# LIS331_Accelerometer.net
KiCad netlist of a schematic drawn in EAGLE
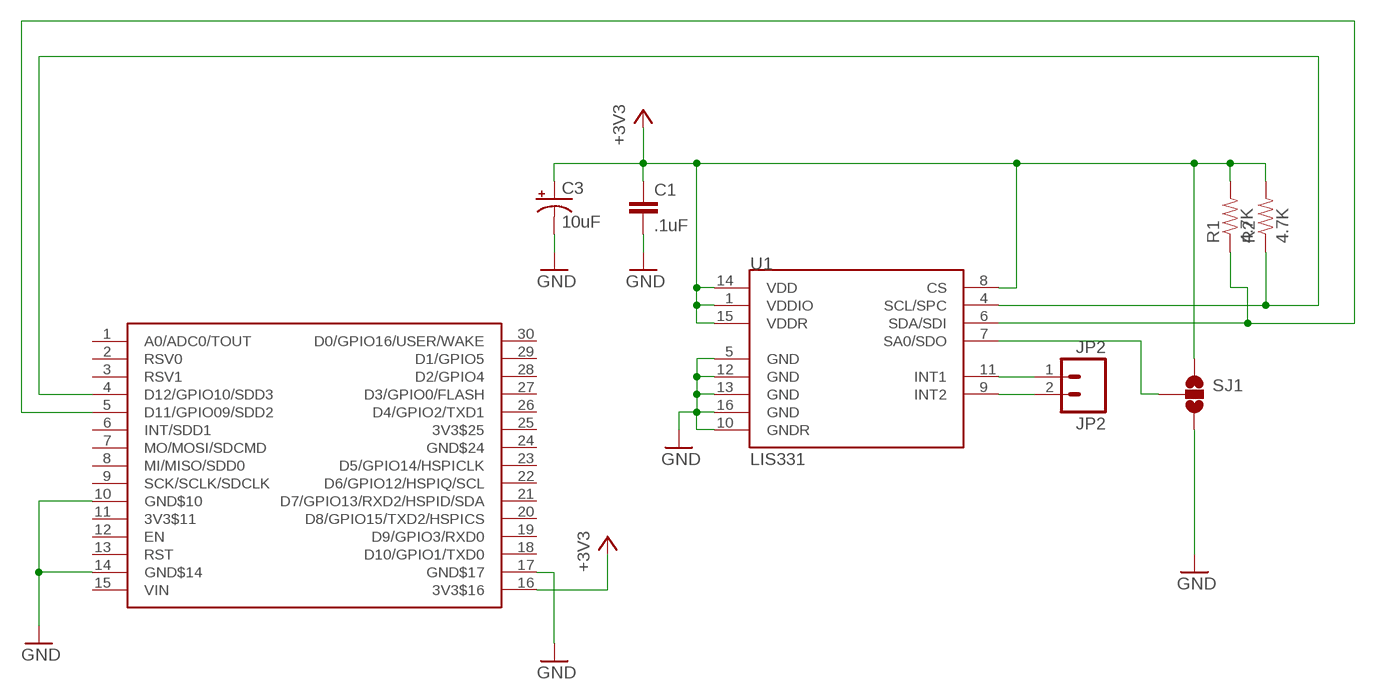
[diagram p0: schematic, sheet 1]

(export (version "E")
  (design (tool "Eeschema 10.0.6"))
  (components
    (comp (ref "C1")
      (value ".1uF")
      (footprint "eagle-import:0603-CAP")
      (libsource (lib "eagle-import") (part "CAP0603-CAP"))
    )
    (comp (ref "C3")
      (value "10uF")
      (footprint "eagle-import:EIA3216")
      (libsource (lib "eagle-import") (part "CAP_POL1206"))
    )
    (comp (ref "JP2")
      (value "JP2")
      (footprint "eagle-import:1X02")
      (libsource (lib "eagle-import") (part "M02PTH"))
    )
    (comp (ref "R1")
      (value "4.7K")
      (footprint "eagle-import:0603-RES")
      (libsource (lib "eagle-import") (part "RESISTOR0603-RES"))
    )
    (comp (ref "R2")
      (value "4.7K")
      (footprint "eagle-import:0603-RES")
      (libsource (lib "eagle-import") (part "RESISTOR0603-RES"))
    )
    (comp (ref "SJ1")
      (value "SOLDERJUMPER_2WAYT")
      (footprint "eagle-import:SJ_2")
      (libsource (lib "eagle-import") (part "SOLDERJUMPER_2WAYT"))
    )
    (comp (ref "U$2")
      (value "NERDSHIELD")
      (footprint "eagle-import:NERDUINO_STACK")
      (libsource (lib "eagle-import") (part "NERDSHIELD"))
    )
    (comp (ref "U1")
      (value "LIS331")
      (footprint "eagle-import:LGA16-3MM")
      (libsource (lib "eagle-import") (part "LIS331"))
    )
  )
  (nets
    (net (code "1") (name "+3V3") (class "Default")
      (node (ref "C1") (pin "1") (pinfunction "1_1") (pintype "passive"))
      (node (ref "C3") (pin "A") (pinfunction "+_A") (pintype "passive"))
      (node (ref "R1") (pin "2") (pinfunction "2_2") (pintype "passive"))
      (node (ref "R2") (pin "2") (pinfunction "2_2") (pintype "passive"))
      (node (ref "SJ1") (pin "1") (pinfunction "1_1") (pintype "passive"))
      (node (ref "U$2") (pin "16") (pinfunction "3V3$16_16") (pintype "bidirectional"))
      (node (ref "U1") (pin "1") (pinfunction "VDDIO_1") (pintype "bidirectional"))
      (node (ref "U1") (pin "14") (pinfunction "VDD_14") (pintype "bidirectional"))
      (node (ref "U1") (pin "15") (pinfunction "VDDR_15") (pintype "bidirectional"))
      (node (ref "U1") (pin "8") (pinfunction "CS_8") (pintype "bidirectional"))
    )
    (net (code "2") (name "GND") (class "Default")
      (node (ref "C1") (pin "2") (pinfunction "2_2") (pintype "passive"))
      (node (ref "C3") (pin "C") (pinfunction "-_C") (pintype "passive"))
      (node (ref "SJ1") (pin "3") (pinfunction "3_3") (pintype "passive"))
      (node (ref "U$2") (pin "10") (pinfunction "GND$10_10") (pintype "bidirectional"))
      (node (ref "U$2") (pin "14") (pinfunction "GND$14_14") (pintype "bidirectional"))
      (node (ref "U$2") (pin "17") (pinfunction "GND$17_17") (pintype "bidirectional"))
      (node (ref "U1") (pin "10") (pinfunction "GNDR_10") (pintype "bidirectional"))
      (node (ref "U1") (pin "12") (pinfunction "GND_12") (pintype "bidirectional"))
      (node (ref "U1") (pin "13") (pinfunction "GND_13") (pintype "bidirectional"))
      (node (ref "U1") (pin "16") (pinfunction "GND_16") (pintype "bidirectional"))
      (node (ref "U1") (pin "5") (pinfunction "GND_5") (pintype "bidirectional"))
    )
    (net (code "3") (name "Net-(U$2-D11{slash}GPIO09{slash}SDD2)") (class "Default")
      (node (ref "R1") (pin "1") (pinfunction "1_1") (pintype "passive"))
      (node (ref "U$2") (pin "5") (pinfunction "D11/GPIO09/SDD2_5") (pintype "bidirectional"))
      (node (ref "U1") (pin "6") (pinfunction "SDA/SDI_6") (pintype "bidirectional"))
    )
    (net (code "4") (name "Net-(U$2-D12{slash}GPIO10{slash}SDD3)") (class "Default")
      (node (ref "R2") (pin "1") (pinfunction "1_1") (pintype "passive"))
      (node (ref "U$2") (pin "4") (pinfunction "D12/GPIO10/SDD3_4") (pintype "bidirectional"))
      (node (ref "U1") (pin "4") (pinfunction "SCL/SPC_4") (pintype "bidirectional"))
    )
    (net (code "5") (name "Net-(U1-INT1)") (class "Default")
      (node (ref "JP2") (pin "1") (pinfunction "1_1") (pintype "passive"))
      (node (ref "U1") (pin "11") (pinfunction "INT1_11") (pintype "bidirectional"))
    )
    (net (code "6") (name "Net-(U1-INT2)") (class "Default")
      (node (ref "JP2") (pin "2") (pinfunction "2_2") (pintype "passive"))
      (node (ref "U1") (pin "9") (pinfunction "INT2_9") (pintype "bidirectional"))
    )
    (net (code "7") (name "Net-(U1-SA0{slash}SDO)") (class "Default")
      (node (ref "SJ1") (pin "2") (pinfunction "2_2") (pintype "passive"))
      (node (ref "U1") (pin "7") (pinfunction "SA0/SDO_7") (pintype "bidirectional"))
    )
    (net (code "8") (name "unconnected-(U$2-3V3$11-Pad11)") (class "Default")
      (node (ref "U$2") (pin "11") (pinfunction "3V3$11_11") (pintype "bidirectional"))
    )
    (net (code "9") (name "unconnected-(U$2-3V3$25-Pad25)") (class "Default")
      (node (ref "U$2") (pin "25") (pinfunction "3V3$25_25") (pintype "bidirectional"))
    )
    (net (code "10") (name "unconnected-(U$2-A0{slash}ADC0{slash}TOUT-Pad1)") (class "Default")
      (node (ref "U$2") (pin "1") (pinfunction "A0/ADC0/TOUT_1") (pintype "bidirectional"))
    )
    (net (code "11") (name "unconnected-(U$2-D0{slash}GPIO16{slash}USER{slash}WAKE-Pad30)") (class "Default")
      (node (ref "U$2") (pin "30") (pinfunction "D0/GPIO16/USER/WAKE_30") (pintype "bidirectional"))
    )
    (net (code "12") (name "unconnected-(U$2-D1{slash}GPIO5-Pad29)") (class "Default")
      (node (ref "U$2") (pin "29") (pinfunction "D1/GPIO5_29") (pintype "bidirectional"))
    )
    (net (code "13") (name "unconnected-(U$2-D2{slash}GPIO4-Pad28)") (class "Default")
      (node (ref "U$2") (pin "28") (pinfunction "D2/GPIO4_28") (pintype "bidirectional"))
    )
    (net (code "14") (name "unconnected-(U$2-D3{slash}GPIO0{slash}FLASH-Pad27)") (class "Default")
      (node (ref "U$2") (pin "27") (pinfunction "D3/GPIO0/FLASH_27") (pintype "bidirectional"))
    )
    (net (code "15") (name "unconnected-(U$2-D4{slash}GPIO2{slash}TXD1-Pad26)") (class "Default")
      (node (ref "U$2") (pin "26") (pinfunction "D4/GPIO2/TXD1_26") (pintype "bidirectional"))
    )
    (net (code "16") (name "unconnected-(U$2-D5{slash}GPIO14{slash}HSPICLK-Pad23)") (class "Default")
      (node (ref "U$2") (pin "23") (pinfunction "D5/GPIO14/HSPICLK_23") (pintype "bidirectional"))
    )
    (net (code "17") (name "unconnected-(U$2-D6{slash}GPIO12{slash}HSPIQ{slash}SCL-Pad22)") (class "Default")
      (node (ref "U$2") (pin "22") (pinfunction "D6/GPIO12/HSPIQ/SCL_22") (pintype "bidirectional"))
    )
    (net (code "18") (name "unconnected-(U$2-D7{slash}GPIO13{slash}RXD2{slash}HSPID{slash}SDA-Pad21)") (class "Default")
      (node (ref "U$2") (pin "21") (pinfunction "D7/GPIO13/RXD2/HSPID/SDA_21") (pintype "bidirectional"))
    )
    (net (code "19") (name "unconnected-(U$2-D8{slash}GPIO15{slash}TXD2{slash}HSPICS-Pad20)") (class "Default")
      (node (ref "U$2") (pin "20") (pinfunction "D8/GPIO15/TXD2/HSPICS_20") (pintype "bidirectional"))
    )
    (net (code "20") (name "unconnected-(U$2-D9{slash}GPIO3{slash}RXD0-Pad19)") (class "Default")
      (node (ref "U$2") (pin "19") (pinfunction "D9/GPIO3/RXD0_19") (pintype "bidirectional"))
    )
    (net (code "21") (name "unconnected-(U$2-D10{slash}GPIO1{slash}TXD0-Pad18)") (class "Default")
      (node (ref "U$2") (pin "18") (pinfunction "D10/GPIO1/TXD0_18") (pintype "bidirectional"))
    )
    (net (code "22") (name "unconnected-(U$2-EN-Pad12)") (class "Default")
      (node (ref "U$2") (pin "12") (pinfunction "EN_12") (pintype "bidirectional"))
    )
    (net (code "23") (name "unconnected-(U$2-GND$24-Pad24)") (class "Default")
      (node (ref "U$2") (pin "24") (pinfunction "GND$24_24") (pintype "bidirectional"))
    )
    (net (code "24") (name "unconnected-(U$2-INT{slash}SDD1-Pad6)") (class "Default")
      (node (ref "U$2") (pin "6") (pinfunction "INT/SDD1_6") (pintype "bidirectional"))
    )
    (net (code "25") (name "unconnected-(U$2-MI{slash}MISO{slash}SDD0-Pad8)") (class "Default")
      (node (ref "U$2") (pin "8") (pinfunction "MI/MISO/SDD0_8") (pintype "bidirectional"))
    )
    (net (code "26") (name "unconnected-(U$2-MO{slash}MOSI{slash}SDCMD-Pad7)") (class "Default")
      (node (ref "U$2") (pin "7") (pinfunction "MO/MOSI/SDCMD_7") (pintype "bidirectional"))
    )
    (net (code "27") (name "unconnected-(U$2-RST-Pad13)") (class "Default")
      (node (ref "U$2") (pin "13") (pinfunction "RST_13") (pintype "bidirectional"))
    )
    (net (code "28") (name "unconnected-(U$2-RSV0-Pad2)") (class "Default")
      (node (ref "U$2") (pin "2") (pinfunction "RSV0_2") (pintype "bidirectional"))
    )
    (net (code "29") (name "unconnected-(U$2-RSV1-Pad3)") (class "Default")
      (node (ref "U$2") (pin "3") (pinfunction "RSV1_3") (pintype "bidirectional"))
    )
    (net (code "30") (name "unconnected-(U$2-SCK{slash}SCLK{slash}SDCLK-Pad9)") (class "Default")
      (node (ref "U$2") (pin "9") (pinfunction "SCK/SCLK/SDCLK_9") (pintype "bidirectional"))
    )
    (net (code "31") (name "unconnected-(U$2-VIN-Pad15)") (class "Default")
      (node (ref "U$2") (pin "15") (pinfunction "VIN_15") (pintype "bidirectional"))
    )
  )
)
